# PWM_PPM_FMU3_REV_G.net
KiCad netlist of a schematic drawn in Altium Designer
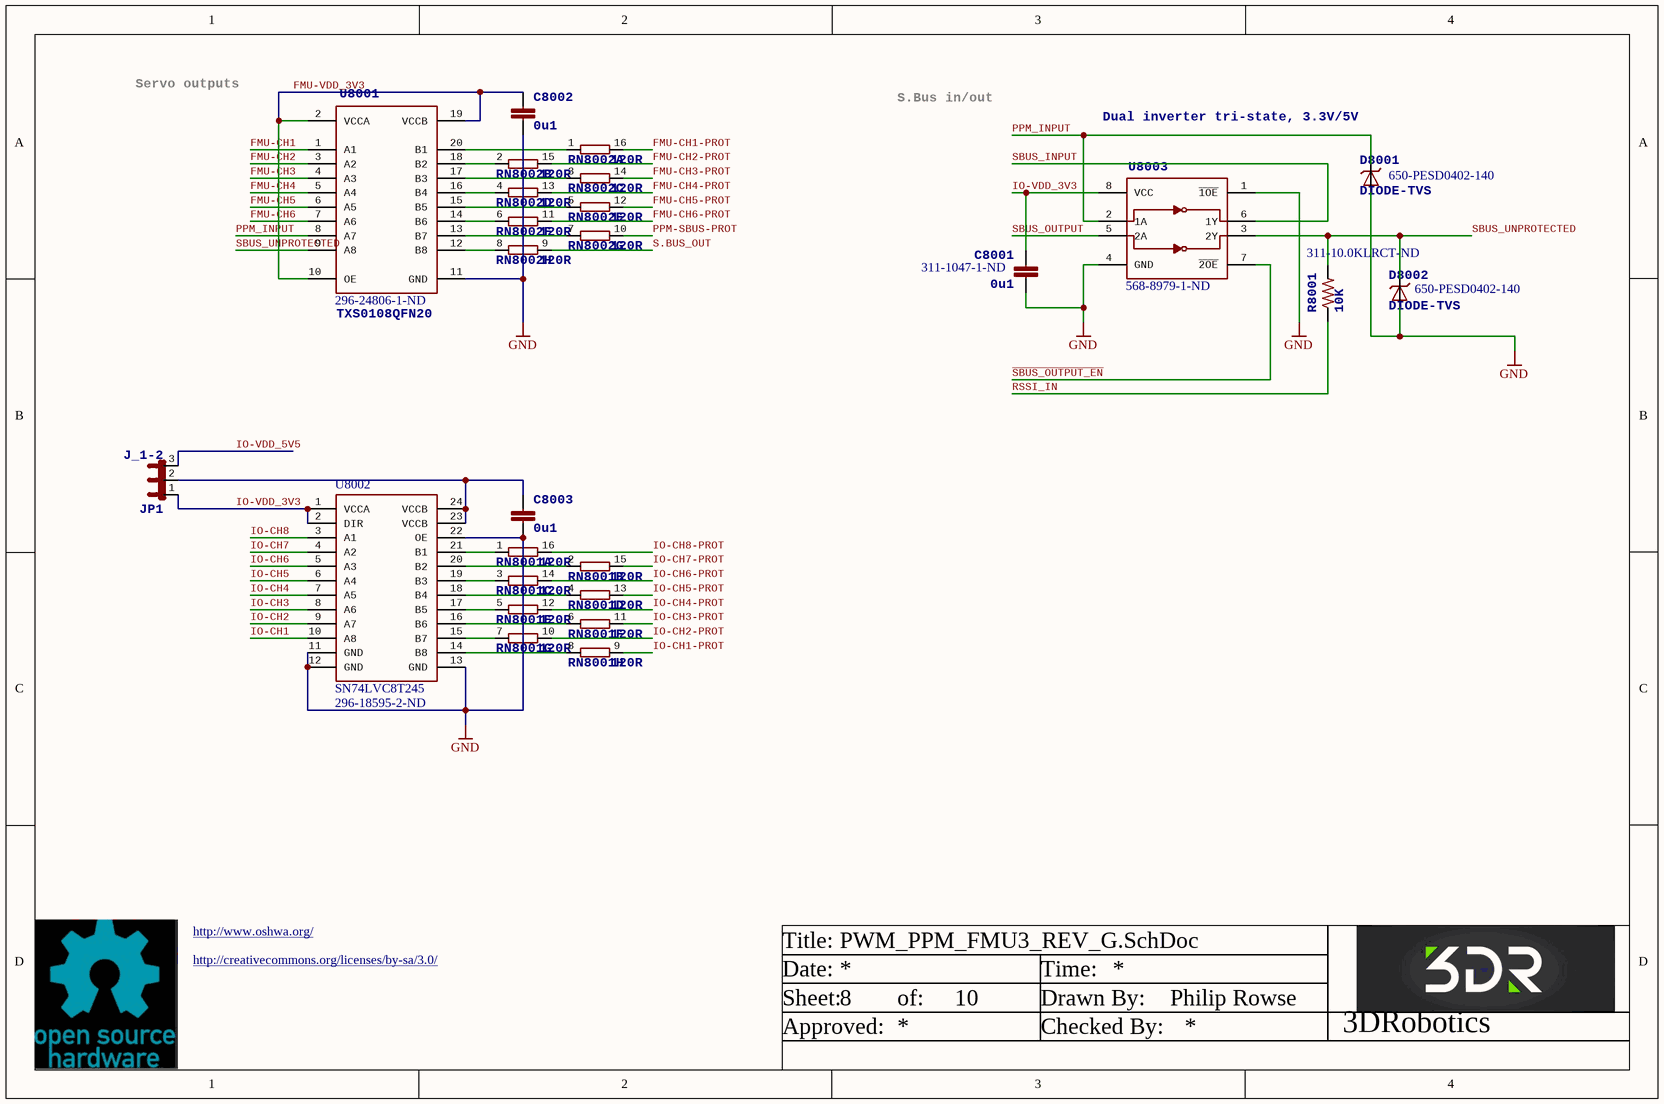
[diagram p0: PWM_PPM_FMU3_REV_G.SchDoc]

(export (version "E")
  (design (tool "Eeschema 10.0.6"))
  (components
    (comp (ref "C8001")
      (value "0u1")
      (footprint "0402-CAP")
      (description "CAP CER 0.1UF 16V Y5V 0402")
      (fields
        (field (name "PARTNO") "CC0402ZRY5V7BB104")
        (field (name "SUPPLIER PART NUMBER 1") "311-1047-1-ND")
        (field (name "3DR_PARTNO") "ECM0700")
      )
      (libsource (lib "") (part "CAP0402_1"))
    )
    (comp (ref "C8002")
      (value "0u1")
      (footprint "0402-CAP")
      (description "CAP CER 0.1UF 16V Y5V 0402")
      (fields (field (name "PARTNO") "CC0402ZRY5V7BB104") (field (name "3DR_PARTNO") "ECM0700"))
      (libsource (lib "pixhawk2") (part "CAP0402"))
    )
    (comp (ref "C8003")
      (value "0u1")
      (footprint "0402-CAP")
      (description "CAP CER 0.1UF 16V Y5V 0402")
      (fields (field (name "PARTNO") "CC0402ZRY5V7BB104") (field (name "3DR_PARTNO") "ECM0700"))
      (libsource (lib "pixhawk2") (part "CAP0402"))
    )
    (comp (ref "D8001")
      (value "DIODE-TVS")
      (footprint "0402-TVS")
      (description "TVS DIODE 14VWM 40VC 0402")
      (fields
        (field (name "SUPPLIER PART NUMBER 1") "650-PESD0402-140")
        (field (name "3DR_PARTNO") "ECM0837")
        (field (name "PARTNO") "PESD0402-140")
      )
      (libsource (lib "pixhawk2") (part "DIODE-TVS"))
    )
    (comp (ref "D8002")
      (value "DIODE-TVS")
      (footprint "0402-TVS")
      (description "TVS DIODE 14VWM 40VC 0402")
      (fields
        (field (name "SUPPLIER PART NUMBER 1") "650-PESD0402-140")
        (field (name "3DR_PARTNO") "ECM0837")
        (field (name "PARTNO") "PESD0402-140")
      )
      (libsource (lib "pixhawk2") (part "DIODE-TVS"))
    )
    (comp (ref "JP1")
      (value "J_1-2")
      (footprint "SJ_3_NO_PLACE_1-2_short")
      (libsource (lib "3DR") (part "JUMPER-31-2"))
    )
    (comp (ref "R8001")
      (value "10K")
      (footprint "0402-RES")
      (description "RES 10K OHM 1/16W 1% 0402 SMD")
      (fields
        (field (name "PARTNO") "RC0402FR-0710KL")
        (field (name "SUPPLIER PART NUMBER 1") "311-10.0KLRCT-ND")
        (field (name "3DR_PARTNO") "ECM0800")
      )
      (libsource (lib "pixhawk2") (part "RESISTOR0402-RES"))
    )
    (comp (ref "RN8001")
      (value "120R")
      (footprint "EXB2HV")
      (description "RES ARRAY 120 OHM 8 RES 1506")
      (fields (field (name "PARTNO") "EXB-2HV121JV") (field (name "3DR_PARTNO") "ECM0266"))
      (libsource (lib "pixhawk2") (part "8R-NEXB2HV-220R"))
    )
    (comp (ref "RN8002")
      (value "120R")
      (footprint "EXB2HV")
      (description "RES ARRAY 120 OHM 8 RES 1506")
      (fields (field (name "PARTNO") "EXB-2HV121JV") (field (name "3DR_PARTNO") "ECM0266"))
      (libsource (lib "pixhawk2") (part "8R-NEXB2HV-220R"))
    )
    (comp (ref "U8001")
      (value "TXS0108QFN20")
      (footprint "QFN20-RGY")
      (description "IC XLATR VOLT-LVL 8B BDIR 20QFN")
      (fields
        (field (name "SUPPLIER PART NUMBER 1") "296-24806-1-ND")
        (field (name "3DR_PARTNO") "ECM0845")
        (field (name "PARTNO") "TXS0108ERGYR")
      )
      (libsource (lib "pixhawk2") (part "TXS0108QFN20"))
    )
    (comp (ref "U8002")
      (value "SN74LVC8T245")
      (footprint "QFN24-RGY")
      (fields (field (name "SUPPLIER PART NUMBER 1") "296-18595-2-ND"))
      (libsource (lib "3DR") (part "SN74LVC8T245"))
    )
    (comp (ref "U8003")
      (value "Dual inverter tri-state, 3.3V/5V")
      (footprint "TSSOP8_SOT505-2")
      (description "IC INVERTER DUAL 4-INPUT 8TSSOP")
      (fields
        (field (name "SUPPLIER PART NUMBER 1") "568-8979-1-ND")
        (field (name "3DR_PARTNO") "ECM0817")
        (field (name "PARTNO") "74LVC2G240DP,125")
      )
      (libsource (lib "pixhawk2") (part "74LVC2G240-TSSOP-8"))
    )
  )
  (nets
    (net (code "1") (name "/FMU-CH1") (class "Default")
      (node (ref "U8001") (pin "1") (pinfunction "A1_1") (pintype "passive"))
    )
    (net (code "2") (name "/FMU-CH1-PROT") (class "Default")
      (node (ref "RN8002") (pin "16") (pinfunction "2_16") (pintype "passive"))
    )
    (net (code "3") (name "/FMU-CH2") (class "Default")
      (node (ref "U8001") (pin "3") (pinfunction "A2_3") (pintype "passive"))
    )
    (net (code "4") (name "/FMU-CH2-PROT") (class "Default")
      (node (ref "RN8002") (pin "15") (pinfunction "2_15") (pintype "passive"))
    )
    (net (code "5") (name "/FMU-CH3") (class "Default")
      (node (ref "U8001") (pin "4") (pinfunction "A3_4") (pintype "passive"))
    )
    (net (code "6") (name "/FMU-CH3-PROT") (class "Default")
      (node (ref "RN8002") (pin "14") (pinfunction "2_14") (pintype "passive"))
    )
    (net (code "7") (name "/FMU-CH4") (class "Default")
      (node (ref "U8001") (pin "5") (pinfunction "A4_5") (pintype "passive"))
    )
    (net (code "8") (name "/FMU-CH4-PROT") (class "Default")
      (node (ref "RN8002") (pin "13") (pinfunction "2_13") (pintype "passive"))
    )
    (net (code "9") (name "/FMU-CH5") (class "Default")
      (node (ref "U8001") (pin "6") (pinfunction "A5_6") (pintype "passive"))
    )
    (net (code "10") (name "/FMU-CH5-PROT") (class "Default")
      (node (ref "RN8002") (pin "12") (pinfunction "2_12") (pintype "passive"))
    )
    (net (code "11") (name "/FMU-CH6") (class "Default")
      (node (ref "U8001") (pin "7") (pinfunction "A6_7") (pintype "passive"))
    )
    (net (code "12") (name "/FMU-CH6-PROT") (class "Default")
      (node (ref "RN8002") (pin "11") (pinfunction "2_11") (pintype "passive"))
    )
    (net (code "13") (name "/FMU-VDD_3V3") (class "Default")
      (node (ref "C8002") (pin "P$1") (pinfunction "1_P$1") (pintype "passive"))
      (node (ref "U8001") (pin "10") (pinfunction "OE_10") (pintype "passive"))
      (node (ref "U8001") (pin "19") (pinfunction "VCCB_19") (pintype "passive"))
      (node (ref "U8001") (pin "2") (pinfunction "VCCA_2") (pintype "passive"))
    )
    (net (code "14") (name "/IO-CH1") (class "Default")
      (node (ref "U8002") (pin "10") (pinfunction "A8_10") (pintype "passive"))
    )
    (net (code "15") (name "/IO-CH1-PROT") (class "Default")
      (node (ref "RN8001") (pin "9") (pinfunction "2_9") (pintype "passive"))
    )
    (net (code "16") (name "/IO-CH2") (class "Default")
      (node (ref "U8002") (pin "9") (pinfunction "A7_9") (pintype "passive"))
    )
    (net (code "17") (name "/IO-CH2-PROT") (class "Default")
      (node (ref "RN8001") (pin "10") (pinfunction "2_10") (pintype "passive"))
    )
    (net (code "18") (name "/IO-CH3") (class "Default")
      (node (ref "U8002") (pin "8") (pinfunction "A6_8") (pintype "passive"))
    )
    (net (code "19") (name "/IO-CH3-PROT") (class "Default")
      (node (ref "RN8001") (pin "11") (pinfunction "2_11") (pintype "passive"))
    )
    (net (code "20") (name "/IO-CH4") (class "Default")
      (node (ref "U8002") (pin "7") (pinfunction "A5_7") (pintype "passive"))
    )
    (net (code "21") (name "/IO-CH4-PROT") (class "Default")
      (node (ref "RN8001") (pin "12") (pinfunction "2_12") (pintype "passive"))
    )
    (net (code "22") (name "/IO-CH5") (class "Default")
      (node (ref "U8002") (pin "6") (pinfunction "A4_6") (pintype "passive"))
    )
    (net (code "23") (name "/IO-CH5-PROT") (class "Default")
      (node (ref "RN8001") (pin "13") (pinfunction "2_13") (pintype "passive"))
    )
    (net (code "24") (name "/IO-CH6") (class "Default")
      (node (ref "U8002") (pin "5") (pinfunction "A3_5") (pintype "passive"))
    )
    (net (code "25") (name "/IO-CH6-PROT") (class "Default")
      (node (ref "RN8001") (pin "14") (pinfunction "2_14") (pintype "passive"))
    )
    (net (code "26") (name "/IO-CH7") (class "Default")
      (node (ref "U8002") (pin "4") (pinfunction "A2_4") (pintype "passive"))
    )
    (net (code "27") (name "/IO-CH7-PROT") (class "Default")
      (node (ref "RN8001") (pin "15") (pinfunction "2_15") (pintype "passive"))
    )
    (net (code "28") (name "/IO-CH8") (class "Default")
      (node (ref "U8002") (pin "3") (pinfunction "A1_3") (pintype "passive"))
    )
    (net (code "29") (name "/IO-CH8-PROT") (class "Default")
      (node (ref "RN8001") (pin "16") (pinfunction "2_16") (pintype "passive"))
    )
    (net (code "30") (name "/IO-VDD_3V3") (class "Default")
      (node (ref "C8001") (pin "P$1") (pinfunction "1_P$1") (pintype "passive"))
      (node (ref "JP1") (pin "1") (pinfunction "1_1") (pintype "passive"))
      (node (ref "U8002") (pin "1") (pinfunction "VCCA_1") (pintype "passive"))
      (node (ref "U8002") (pin "2") (pinfunction "DIR_2") (pintype "passive"))
      (node (ref "U8003") (pin "8") (pinfunction "VCC_8") (pintype "open_emitter"))
    )
    (net (code "31") (name "/IO-VDD_5V5") (class "Default")
      (node (ref "JP1") (pin "3") (pinfunction "3_3") (pintype "passive"))
    )
    (net (code "32") (name "/PPM-SBUS-PROT") (class "Default")
      (node (ref "RN8002") (pin "10") (pinfunction "2_10") (pintype "passive"))
    )
    (net (code "33") (name "/PPM_INPUT") (class "Default")
      (node (ref "D8001") (pin "C") (pinfunction "C_C") (pintype "passive"))
      (node (ref "U8001") (pin "8") (pinfunction "A7_8") (pintype "passive"))
      (node (ref "U8003") (pin "2") (pinfunction "1A_2") (pintype "passive"))
    )
    (net (code "34") (name "/RSSI_IN") (class "Default")
      (node (ref "R8001") (pin "P$1") (pinfunction "1_P$1") (pintype "passive"))
    )
    (net (code "35") (name "/S.BUS_OUT") (class "Default")
      (node (ref "RN8002") (pin "9") (pinfunction "2_9") (pintype "passive"))
    )
    (net (code "36") (name "/SBUS_INPUT") (class "Default")
      (node (ref "U8003") (pin "6") (pinfunction "1Y_6") (pintype "passive"))
    )
    (net (code "37") (name "/SBUS_OUTPUT") (class "Default")
      (node (ref "U8003") (pin "5") (pinfunction "2A_5") (pintype "passive"))
    )
    (net (code "38") (name "/SBUS_UNPROTECTED") (class "Default")
      (node (ref "D8002") (pin "C") (pinfunction "C_C") (pintype "passive"))
      (node (ref "R8001") (pin "P$2") (pinfunction "2_P$2") (pintype "passive"))
      (node (ref "U8001") (pin "9") (pinfunction "A8_9") (pintype "passive"))
      (node (ref "U8003") (pin "3") (pinfunction "2Y_3") (pintype "passive"))
    )
    (net (code "39") (name "/~{SBUS_OUTPUT_EN}") (class "Default")
      (node (ref "U8003") (pin "7") (pinfunction "~{2OE}_7") (pintype "passive"))
    )
    (net (code "40") (name "GND") (class "Default")
      (node (ref "C8001") (pin "P$2") (pinfunction "2_P$2") (pintype "passive"))
      (node (ref "C8002") (pin "P$2") (pinfunction "2_P$2") (pintype "passive"))
      (node (ref "C8003") (pin "P$2") (pinfunction "2_P$2") (pintype "passive"))
      (node (ref "D8001") (pin "A") (pinfunction "A_A") (pintype "passive"))
      (node (ref "D8002") (pin "A") (pinfunction "A_A") (pintype "passive"))
      (node (ref "U8001") (pin "11") (pinfunction "GND_11") (pintype "open_emitter"))
      (node (ref "U8002") (pin "11") (pinfunction "GND_11") (pintype "open_emitter"))
      (node (ref "U8002") (pin "12") (pinfunction "GND_12") (pintype "open_emitter"))
      (node (ref "U8002") (pin "13") (pinfunction "GND_13") (pintype "open_emitter"))
      (node (ref "U8002") (pin "22") (pinfunction "OE_22") (pintype "passive"))
      (node (ref "U8003") (pin "1") (pinfunction "~{1OE}_1") (pintype "passive"))
      (node (ref "U8003") (pin "4") (pinfunction "GND_4") (pintype "open_emitter"))
    )
    (net (code "41") (name "Net-(C8003-1)") (class "Default")
      (node (ref "C8003") (pin "P$1") (pinfunction "1_P$1") (pintype "passive"))
      (node (ref "JP1") (pin "2") (pinfunction "2_2") (pintype "passive"))
      (node (ref "U8002") (pin "23") (pinfunction "VCCB_23") (pintype "passive"))
      (node (ref "U8002") (pin "24") (pinfunction "VCCB_24") (pintype "passive"))
    )
    (net (code "42") (name "Net-(RN8001B-1)") (class "Default")
      (node (ref "RN8001") (pin "2") (pinfunction "1_2") (pintype "passive"))
      (node (ref "U8002") (pin "20") (pinfunction "B2_20") (pintype "passive"))
    )
    (net (code "43") (name "Net-(RN8001C-1)") (class "Default")
      (node (ref "RN8001") (pin "3") (pinfunction "1_3") (pintype "passive"))
      (node (ref "U8002") (pin "19") (pinfunction "B3_19") (pintype "passive"))
    )
    (net (code "44") (name "Net-(RN8001D-1)") (class "Default")
      (node (ref "RN8001") (pin "4") (pinfunction "1_4") (pintype "passive"))
      (node (ref "U8002") (pin "18") (pinfunction "B4_18") (pintype "passive"))
    )
    (net (code "45") (name "Net-(RN8001E-1)") (class "Default")
      (node (ref "RN8001") (pin "5") (pinfunction "1_5") (pintype "passive"))
      (node (ref "U8002") (pin "17") (pinfunction "B5_17") (pintype "passive"))
    )
    (net (code "46") (name "Net-(RN8001F-1)") (class "Default")
      (node (ref "RN8001") (pin "6") (pinfunction "1_6") (pintype "passive"))
      (node (ref "U8002") (pin "16") (pinfunction "B6_16") (pintype "passive"))
    )
    (net (code "47") (name "Net-(RN8001G-1)") (class "Default")
      (node (ref "RN8001") (pin "7") (pinfunction "1_7") (pintype "passive"))
      (node (ref "U8002") (pin "15") (pinfunction "B7_15") (pintype "passive"))
    )
    (net (code "48") (name "Net-(RN8001H-1)") (class "Default")
      (node (ref "RN8001") (pin "8") (pinfunction "1_8") (pintype "passive"))
      (node (ref "U8002") (pin "14") (pinfunction "B8_14") (pintype "passive"))
    )
    (net (code "49") (name "Net-(RN8002B-1)") (class "Default")
      (node (ref "RN8002") (pin "2") (pinfunction "1_2") (pintype "passive"))
      (node (ref "U8001") (pin "18") (pinfunction "B2_18") (pintype "passive"))
    )
    (net (code "50") (name "Net-(RN8002C-1)") (class "Default")
      (node (ref "RN8002") (pin "3") (pinfunction "1_3") (pintype "passive"))
      (node (ref "U8001") (pin "17") (pinfunction "B3_17") (pintype "passive"))
    )
    (net (code "51") (name "Net-(RN8002D-1)") (class "Default")
      (node (ref "RN8002") (pin "4") (pinfunction "1_4") (pintype "passive"))
      (node (ref "U8001") (pin "16") (pinfunction "B4_16") (pintype "passive"))
    )
    (net (code "52") (name "Net-(RN8002E-1)") (class "Default")
      (node (ref "RN8002") (pin "5") (pinfunction "1_5") (pintype "passive"))
      (node (ref "U8001") (pin "15") (pinfunction "B5_15") (pintype "passive"))
    )
    (net (code "53") (name "Net-(RN8002F-1)") (class "Default")
      (node (ref "RN8002") (pin "6") (pinfunction "1_6") (pintype "passive"))
      (node (ref "U8001") (pin "14") (pinfunction "B6_14") (pintype "passive"))
    )
    (net (code "54") (name "Net-(RN8002G-1)") (class "Default")
      (node (ref "RN8002") (pin "7") (pinfunction "1_7") (pintype "passive"))
      (node (ref "U8001") (pin "13") (pinfunction "B7_13") (pintype "passive"))
    )
    (net (code "55") (name "Net-(RN8002H-1)") (class "Default")
      (node (ref "RN8002") (pin "8") (pinfunction "1_8") (pintype "passive"))
      (node (ref "U8001") (pin "12") (pinfunction "B8_12") (pintype "passive"))
    )
    (net (code "56") (name "Net-(U8001-B1)") (class "Default")
      (node (ref "RN8002") (pin "1") (pinfunction "1_1") (pintype "passive"))
      (node (ref "U8001") (pin "20") (pinfunction "B1_20") (pintype "passive"))
    )
    (net (code "57") (name "Net-(U8002-B1)") (class "Default")
      (node (ref "RN8001") (pin "1") (pinfunction "1_1") (pintype "passive"))
      (node (ref "U8002") (pin "21") (pinfunction "B1_21") (pintype "passive"))
    )
  )
)
